# POV_2_0.net
KiCad netlist of a schematic drawn in EAGLE
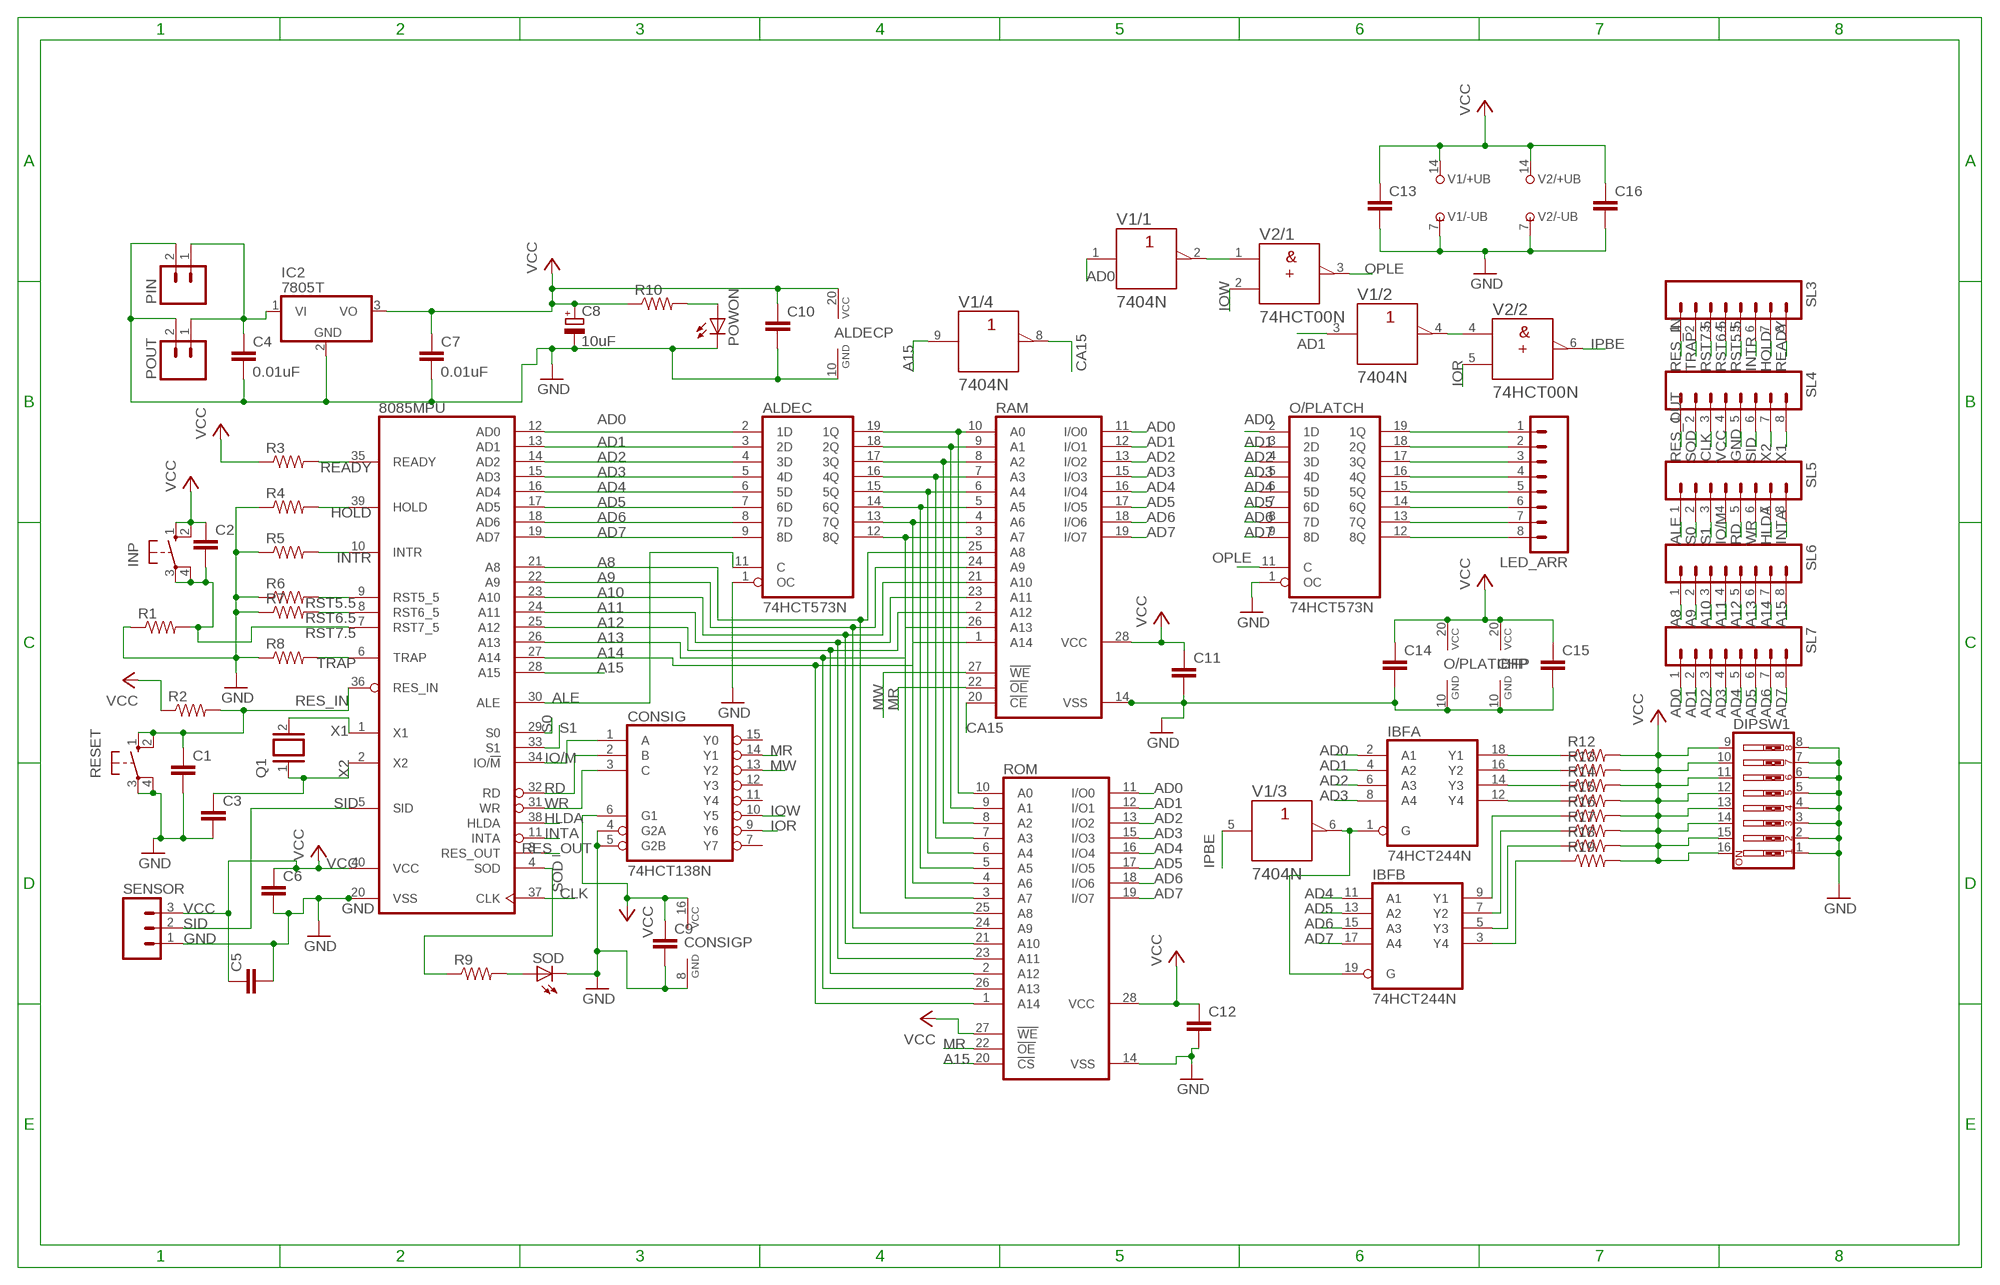
[diagram p0: schematic, sheet 1]

(export (version "E")
  (design (tool "Eeschema 10.0.6"))
  (components
    (comp (ref "8085MPU")
      (value "8085")
      (footprint "eagle-import:DIL40")
      (libsource (lib "eagle-import") (part "8085"))
    )
    (comp (ref "ALDEC")
      (value "74HCT573N")
      (footprint "eagle-import:DIL20")
      (libsource (lib "eagle-import") (part "74573NHCT"))
    )
    (comp (ref "C1")
      (value "C-EU025-024X044")
      (footprint "eagle-import:C025-024X044")
      (libsource (lib "eagle-import") (part "C-EU025-024X044"))
    )
    (comp (ref "C2")
      (value "C-EU025-024X044")
      (footprint "eagle-import:C025-024X044")
      (libsource (lib "eagle-import") (part "C-EU025-024X044"))
    )
    (comp (ref "C3")
      (value "C-EU025-024X044")
      (footprint "eagle-import:C025-024X044")
      (libsource (lib "eagle-import") (part "C-EU025-024X044"))
    )
    (comp (ref "C4")
      (value "0.01uF")
      (footprint "eagle-import:C025-024X044")
      (libsource (lib "eagle-import") (part "C-EU025-024X044"))
    )
    (comp (ref "C5")
      (value "C-EU025-024X044")
      (footprint "eagle-import:C025-024X044")
      (libsource (lib "eagle-import") (part "C-EU025-024X044"))
    )
    (comp (ref "C6")
      (value "C-EU025-024X044")
      (footprint "eagle-import:C025-024X044")
      (libsource (lib "eagle-import") (part "C-EU025-024X044"))
    )
    (comp (ref "C7")
      (value "0.01uF")
      (footprint "eagle-import:C025-024X044")
      (libsource (lib "eagle-import") (part "C-EU025-024X044"))
    )
    (comp (ref "C8")
      (value "10uF")
      (footprint "eagle-import:E2,5-6E")
      (libsource (lib "eagle-import") (part "CPOL-EUE2,5-6E"))
    )
    (comp (ref "C9")
      (value "C-EU025-024X044")
      (footprint "eagle-import:C025-024X044")
      (libsource (lib "eagle-import") (part "C-EU025-024X044"))
    )
    (comp (ref "C10")
      (value "C-EU025-024X044")
      (footprint "eagle-import:C025-024X044")
      (libsource (lib "eagle-import") (part "C-EU025-024X044"))
    )
    (comp (ref "C11")
      (value "C-EU025-024X044")
      (footprint "eagle-import:C025-024X044")
      (libsource (lib "eagle-import") (part "C-EU025-024X044"))
    )
    (comp (ref "C12")
      (value "C-EU025-024X044")
      (footprint "eagle-import:C025-024X044")
      (libsource (lib "eagle-import") (part "C-EU025-024X044"))
    )
    (comp (ref "C13")
      (value "C-EU025-024X044")
      (footprint "eagle-import:C025-024X044")
      (libsource (lib "eagle-import") (part "C-EU025-024X044"))
    )
    (comp (ref "C14")
      (value "C-EU025-024X044")
      (footprint "eagle-import:C025-024X044")
      (libsource (lib "eagle-import") (part "C-EU025-024X044"))
    )
    (comp (ref "C15")
      (value "C-EU025-024X044")
      (footprint "eagle-import:C025-024X044")
      (libsource (lib "eagle-import") (part "C-EU025-024X044"))
    )
    (comp (ref "C16")
      (value "C-EU025-024X044")
      (footprint "eagle-import:C025-024X044")
      (libsource (lib "eagle-import") (part "C-EU025-024X044"))
    )
    (comp (ref "CONSIG")
      (value "74HCT138N")
      (footprint "eagle-import:DIL16")
      (libsource (lib "eagle-import") (part "74138NHCT"))
    )
    (comp (ref "DIPSW1")
      (value "SW_DIP-8")
      (footprint "eagle-import:EDG-08")
      (libsource (lib "eagle-import") (part "SW_DIP-8"))
    )
    (comp (ref "IBF")
      (value "74HCT244N")
      (footprint "eagle-import:DIL20")
      (libsource (lib "eagle-import") (part "74244NHCT"))
    )
    (comp (ref "IC2")
      (value "7805T")
      (footprint "eagle-import:TO220H")
      (libsource (lib "eagle-import") (part "78T05"))
    )
    (comp (ref "INP")
      (value "10-XX")
      (footprint "eagle-import:B3F-10XX")
      (fields (field (name "MPN") "B3F-1000"))
      (libsource (lib "eagle-import") (part "10-XX"))
    )
    (comp (ref "LED_ARR")
      (value "M08")
      (footprint "eagle-import:08P")
      (libsource (lib "eagle-import") (part "M08"))
    )
    (comp (ref "O/PLATCH")
      (value "74HCT573N")
      (footprint "eagle-import:DIL20")
      (libsource (lib "eagle-import") (part "74573NHCT"))
    )
    (comp (ref "PIN")
      (value "M02")
      (footprint "eagle-import:02P")
      (libsource (lib "eagle-import") (part "M02"))
    )
    (comp (ref "POUT")
      (value "M02")
      (footprint "eagle-import:02P")
      (libsource (lib "eagle-import") (part "M02"))
    )
    (comp (ref "POWON")
      (value "LED5MM")
      (footprint "eagle-import:LED5MM")
      (libsource (lib "eagle-import") (part "LED5MM"))
    )
    (comp (ref "Q1")
      (value "XTAL/S")
      (footprint "eagle-import:QS")
      (libsource (lib "eagle-import") (part "XTAL/S"))
    )
    (comp (ref "R1")
      (value "R-US_0204/7")
      (footprint "eagle-import:0204_7")
      (libsource (lib "eagle-import") (part "R-US_0204/7"))
    )
    (comp (ref "R2")
      (value "R-US_0204/7")
      (footprint "eagle-import:0204_7")
      (libsource (lib "eagle-import") (part "R-US_0204/7"))
    )
    (comp (ref "R3")
      (value "R-US_0204/7")
      (footprint "eagle-import:0204_7")
      (libsource (lib "eagle-import") (part "R-US_0204/7"))
    )
    (comp (ref "R4")
      (value "R-US_0204/7")
      (footprint "eagle-import:0204_7")
      (libsource (lib "eagle-import") (part "R-US_0204/7"))
    )
    (comp (ref "R5")
      (value "R-US_0204/7")
      (footprint "eagle-import:0204_7")
      (libsource (lib "eagle-import") (part "R-US_0204/7"))
    )
    (comp (ref "R6")
      (value "R-US_0204/7")
      (footprint "eagle-import:0204_7")
      (libsource (lib "eagle-import") (part "R-US_0204/7"))
    )
    (comp (ref "R7")
      (value "R-US_0204/7")
      (footprint "eagle-import:0204_7")
      (libsource (lib "eagle-import") (part "R-US_0204/7"))
    )
    (comp (ref "R8")
      (value "R-US_0204/7")
      (footprint "eagle-import:0204_7")
      (libsource (lib "eagle-import") (part "R-US_0204/7"))
    )
    (comp (ref "R9")
      (value "R-US_0204/7")
      (footprint "eagle-import:0204_7")
      (libsource (lib "eagle-import") (part "R-US_0204/7"))
    )
    (comp (ref "R10")
      (value "R-US_0204/7")
      (footprint "eagle-import:0204_7")
      (libsource (lib "eagle-import") (part "R-US_0204/7"))
    )
    (comp (ref "R12")
      (value "R-US_0204/7")
      (footprint "eagle-import:0204_7")
      (libsource (lib "eagle-import") (part "R-US_0204/7"))
    )
    (comp (ref "R13")
      (value "R-US_0204/7")
      (footprint "eagle-import:0204_7")
      (libsource (lib "eagle-import") (part "R-US_0204/7"))
    )
    (comp (ref "R14")
      (value "R-US_0204/7")
      (footprint "eagle-import:0204_7")
      (libsource (lib "eagle-import") (part "R-US_0204/7"))
    )
    (comp (ref "R15")
      (value "R-US_0204/7")
      (footprint "eagle-import:0204_7")
      (libsource (lib "eagle-import") (part "R-US_0204/7"))
    )
    (comp (ref "R16")
      (value "R-US_0204/7")
      (footprint "eagle-import:0204_7")
      (libsource (lib "eagle-import") (part "R-US_0204/7"))
    )
    (comp (ref "R17")
      (value "R-US_0204/7")
      (footprint "eagle-import:0204_7")
      (libsource (lib "eagle-import") (part "R-US_0204/7"))
    )
    (comp (ref "R18")
      (value "R-US_0204/7")
      (footprint "eagle-import:0204_7")
      (libsource (lib "eagle-import") (part "R-US_0204/7"))
    )
    (comp (ref "R19")
      (value "R-US_0204/7")
      (footprint "eagle-import:0204_7")
      (libsource (lib "eagle-import") (part "R-US_0204/7"))
    )
    (comp (ref "RAM")
      (value "58C256P")
      (footprint "eagle-import:DIL28-6")
      (fields (field (name "MPN") "HN58C256AP85E"))
      (libsource (lib "eagle-import") (part "58C256P"))
    )
    (comp (ref "RESET")
      (value "10-XX")
      (footprint "eagle-import:B3F-10XX")
      (fields (field (name "MPN") "B3F-1000"))
      (libsource (lib "eagle-import") (part "10-XX"))
    )
    (comp (ref "ROM")
      (value "62256P")
      (footprint "eagle-import:DIL28-6")
      (libsource (lib "eagle-import") (part "62256P"))
    )
    (comp (ref "SENSOR")
      (value "M03")
      (footprint "eagle-import:03P")
      (libsource (lib "eagle-import") (part "M03"))
    )
    (comp (ref "SL3")
      (value "M08")
      (footprint "eagle-import:08P")
      (libsource (lib "eagle-import") (part "M08"))
    )
    (comp (ref "SL4")
      (value "M08")
      (footprint "eagle-import:08P")
      (libsource (lib "eagle-import") (part "M08"))
    )
    (comp (ref "SL5")
      (value "M08")
      (footprint "eagle-import:08P")
      (libsource (lib "eagle-import") (part "M08"))
    )
    (comp (ref "SL6")
      (value "M08")
      (footprint "eagle-import:08P")
      (libsource (lib "eagle-import") (part "M08"))
    )
    (comp (ref "SL7")
      (value "M08")
      (footprint "eagle-import:08P")
      (libsource (lib "eagle-import") (part "M08"))
    )
    (comp (ref "SOD")
      (value "LED5MM")
      (footprint "eagle-import:LED5MM")
      (libsource (lib "eagle-import") (part "LED5MM"))
    )
    (comp (ref "V1")
      (value "7404N")
      (footprint "eagle-import:DIL14")
      (libsource (lib "eagle-import") (part "7404N"))
    )
    (comp (ref "V2")
      (value "74HCT00N")
      (footprint "eagle-import:DIL14")
      (libsource (lib "eagle-import") (part "7400NHCT"))
    )
  )
  (nets
    (net (code "1") (name "/A8") (class "Default")
      (node (ref "8085MPU") (pin "21") (pinfunction "A8_21") (pintype "output"))
      (node (ref "RAM") (pin "25") (pinfunction "A8_25") (pintype "input"))
      (node (ref "ROM") (pin "25") (pinfunction "A8_25") (pintype "input"))
      (node (ref "SL6") (pin "1") (pinfunction "1_1") (pintype "passive"))
    )
    (net (code "2") (name "/A9") (class "Default")
      (node (ref "8085MPU") (pin "22") (pinfunction "A9_22") (pintype "output"))
      (node (ref "RAM") (pin "24") (pinfunction "A9_24") (pintype "input"))
      (node (ref "ROM") (pin "24") (pinfunction "A9_24") (pintype "input"))
      (node (ref "SL6") (pin "2") (pinfunction "2_2") (pintype "passive"))
    )
    (net (code "3") (name "/A10") (class "Default")
      (node (ref "8085MPU") (pin "23") (pinfunction "A10_23") (pintype "output"))
      (node (ref "RAM") (pin "21") (pinfunction "A10_21") (pintype "input"))
      (node (ref "ROM") (pin "21") (pinfunction "A10_21") (pintype "input"))
      (node (ref "SL6") (pin "3") (pinfunction "3_3") (pintype "passive"))
    )
    (net (code "4") (name "/A11") (class "Default")
      (node (ref "8085MPU") (pin "24") (pinfunction "A11_24") (pintype "output"))
      (node (ref "RAM") (pin "23") (pinfunction "A11_23") (pintype "input"))
      (node (ref "ROM") (pin "23") (pinfunction "A11_23") (pintype "input"))
      (node (ref "SL6") (pin "4") (pinfunction "4_4") (pintype "passive"))
    )
    (net (code "5") (name "/A12") (class "Default")
      (node (ref "8085MPU") (pin "25") (pinfunction "A12_25") (pintype "output"))
      (node (ref "RAM") (pin "2") (pinfunction "A12_2") (pintype "input"))
      (node (ref "ROM") (pin "2") (pinfunction "A12_2") (pintype "input"))
      (node (ref "SL6") (pin "5") (pinfunction "5_5") (pintype "passive"))
    )
    (net (code "6") (name "/A13") (class "Default")
      (node (ref "8085MPU") (pin "26") (pinfunction "A13_26") (pintype "output"))
      (node (ref "RAM") (pin "26") (pinfunction "A13_26") (pintype "input"))
      (node (ref "ROM") (pin "26") (pinfunction "A13_26") (pintype "input"))
      (node (ref "SL6") (pin "6") (pinfunction "6_6") (pintype "passive"))
    )
    (net (code "7") (name "/A14") (class "Default")
      (node (ref "8085MPU") (pin "27") (pinfunction "A14_27") (pintype "output"))
      (node (ref "RAM") (pin "1") (pinfunction "A14_1") (pintype "input"))
      (node (ref "ROM") (pin "1") (pinfunction "A14_1") (pintype "input"))
      (node (ref "SL6") (pin "7") (pinfunction "7_7") (pintype "passive"))
    )
    (net (code "8") (name "/A15") (class "Default")
      (node (ref "8085MPU") (pin "28") (pinfunction "A15_28") (pintype "output"))
      (node (ref "ROM") (pin "20") (pinfunction "~{CS}_20") (pintype "input"))
      (node (ref "SL6") (pin "8") (pinfunction "8_8") (pintype "passive"))
      (node (ref "V1") (pin "9") (pinfunction "A_9") (pintype "input"))
    )
    (net (code "9") (name "/AD0") (class "Default")
      (node (ref "8085MPU") (pin "12") (pinfunction "AD0_12") (pintype "bidirectional"))
      (node (ref "ALDEC") (pin "2") (pinfunction "1D_2") (pintype "input"))
      (node (ref "IBF") (pin "2") (pinfunction "A1_2") (pintype "input"))
      (node (ref "O/PLATCH") (pin "2") (pinfunction "1D_2") (pintype "input"))
      (node (ref "RAM") (pin "11") (pinfunction "I/O0_11") (pintype "tri_state"))
      (node (ref "ROM") (pin "11") (pinfunction "I/O0_11") (pintype "bidirectional"))
      (node (ref "SL7") (pin "1") (pinfunction "1_1") (pintype "passive"))
      (node (ref "V1") (pin "1") (pinfunction "A_1") (pintype "input"))
    )
    (net (code "10") (name "/AD1") (class "Default")
      (node (ref "8085MPU") (pin "13") (pinfunction "AD1_13") (pintype "bidirectional"))
      (node (ref "ALDEC") (pin "3") (pinfunction "2D_3") (pintype "input"))
      (node (ref "IBF") (pin "4") (pinfunction "A2_4") (pintype "input"))
      (node (ref "O/PLATCH") (pin "3") (pinfunction "2D_3") (pintype "input"))
      (node (ref "RAM") (pin "12") (pinfunction "I/O1_12") (pintype "tri_state"))
      (node (ref "ROM") (pin "12") (pinfunction "I/O1_12") (pintype "bidirectional"))
      (node (ref "SL7") (pin "2") (pinfunction "2_2") (pintype "passive"))
      (node (ref "V1") (pin "3") (pinfunction "A_3") (pintype "input"))
    )
    (net (code "11") (name "/AD2") (class "Default")
      (node (ref "8085MPU") (pin "14") (pinfunction "AD2_14") (pintype "bidirectional"))
      (node (ref "ALDEC") (pin "4") (pinfunction "3D_4") (pintype "input"))
      (node (ref "IBF") (pin "6") (pinfunction "A3_6") (pintype "input"))
      (node (ref "O/PLATCH") (pin "4") (pinfunction "3D_4") (pintype "input"))
      (node (ref "RAM") (pin "13") (pinfunction "I/O2_13") (pintype "tri_state"))
      (node (ref "ROM") (pin "13") (pinfunction "I/O2_13") (pintype "bidirectional"))
      (node (ref "SL7") (pin "3") (pinfunction "3_3") (pintype "passive"))
    )
    (net (code "12") (name "/AD3") (class "Default")
      (node (ref "8085MPU") (pin "15") (pinfunction "AD3_15") (pintype "bidirectional"))
      (node (ref "ALDEC") (pin "5") (pinfunction "4D_5") (pintype "input"))
      (node (ref "IBF") (pin "8") (pinfunction "A4_8") (pintype "input"))
      (node (ref "O/PLATCH") (pin "5") (pinfunction "4D_5") (pintype "input"))
      (node (ref "RAM") (pin "15") (pinfunction "I/O3_15") (pintype "tri_state"))
      (node (ref "ROM") (pin "15") (pinfunction "I/O3_15") (pintype "bidirectional"))
      (node (ref "SL7") (pin "4") (pinfunction "4_4") (pintype "passive"))
    )
    (net (code "13") (name "/AD4") (class "Default")
      (node (ref "8085MPU") (pin "16") (pinfunction "AD4_16") (pintype "bidirectional"))
      (node (ref "ALDEC") (pin "6") (pinfunction "5D_6") (pintype "input"))
      (node (ref "IBF") (pin "11") (pinfunction "A1_11") (pintype "input"))
      (node (ref "O/PLATCH") (pin "6") (pinfunction "5D_6") (pintype "input"))
      (node (ref "RAM") (pin "16") (pinfunction "I/O4_16") (pintype "tri_state"))
      (node (ref "ROM") (pin "16") (pinfunction "I/O4_16") (pintype "bidirectional"))
      (node (ref "SL7") (pin "5") (pinfunction "5_5") (pintype "passive"))
    )
    (net (code "14") (name "/AD5") (class "Default")
      (node (ref "8085MPU") (pin "17") (pinfunction "AD5_17") (pintype "bidirectional"))
      (node (ref "ALDEC") (pin "7") (pinfunction "6D_7") (pintype "input"))
      (node (ref "IBF") (pin "13") (pinfunction "A2_13") (pintype "input"))
      (node (ref "O/PLATCH") (pin "7") (pinfunction "6D_7") (pintype "input"))
      (node (ref "RAM") (pin "17") (pinfunction "I/O5_17") (pintype "tri_state"))
      (node (ref "ROM") (pin "17") (pinfunction "I/O5_17") (pintype "bidirectional"))
      (node (ref "SL7") (pin "6") (pinfunction "6_6") (pintype "passive"))
    )
    (net (code "15") (name "/AD6") (class "Default")
      (node (ref "8085MPU") (pin "18") (pinfunction "AD6_18") (pintype "bidirectional"))
      (node (ref "ALDEC") (pin "8") (pinfunction "7D_8") (pintype "input"))
      (node (ref "IBF") (pin "15") (pinfunction "A3_15") (pintype "input"))
      (node (ref "O/PLATCH") (pin "8") (pinfunction "7D_8") (pintype "input"))
      (node (ref "RAM") (pin "18") (pinfunction "I/O6_18") (pintype "tri_state"))
      (node (ref "ROM") (pin "18") (pinfunction "I/O6_18") (pintype "bidirectional"))
      (node (ref "SL7") (pin "7") (pinfunction "7_7") (pintype "passive"))
    )
    (net (code "16") (name "/AD7") (class "Default")
      (node (ref "8085MPU") (pin "19") (pinfunction "AD7_19") (pintype "bidirectional"))
      (node (ref "ALDEC") (pin "9") (pinfunction "8D_9") (pintype "input"))
      (node (ref "IBF") (pin "17") (pinfunction "A4_17") (pintype "input"))
      (node (ref "O/PLATCH") (pin "9") (pinfunction "8D_9") (pintype "input"))
      (node (ref "RAM") (pin "19") (pinfunction "I/O7_19") (pintype "tri_state"))
      (node (ref "ROM") (pin "19") (pinfunction "I/O7_19") (pintype "bidirectional"))
      (node (ref "SL7") (pin "8") (pinfunction "8_8") (pintype "passive"))
    )
    (net (code "17") (name "/ALE") (class "Default")
      (node (ref "8085MPU") (pin "30") (pinfunction "ALE_30") (pintype "output"))
      (node (ref "ALDEC") (pin "11") (pinfunction "C_11") (pintype "input"))
      (node (ref "SL5") (pin "1") (pinfunction "1_1") (pintype "passive"))
    )
    (net (code "18") (name "/CA15") (class "Default")
      (node (ref "RAM") (pin "20") (pinfunction "~{CE}_20") (pintype "input"))
      (node (ref "V1") (pin "8") (pinfunction "Y_8") (pintype "output"))
    )
    (net (code "19") (name "/CLK") (class "Default")
      (node (ref "8085MPU") (pin "37") (pinfunction "CLK_37") (pintype "output"))
      (node (ref "SL4") (pin "3") (pinfunction "3_3") (pintype "passive"))
    )
    (net (code "20") (name "/HLDA") (class "Default")
      (node (ref "8085MPU") (pin "38") (pinfunction "HLDA_38") (pintype "output"))
      (node (ref "SL5") (pin "7") (pinfunction "7_7") (pintype "passive"))
    )
    (net (code "21") (name "/HOLD") (class "Default")
      (node (ref "8085MPU") (pin "39") (pinfunction "HOLD_39") (pintype "input"))
      (node (ref "R4") (pin "2") (pinfunction "2_2") (pintype "passive"))
      (node (ref "SL3") (pin "7") (pinfunction "7_7") (pintype "passive"))
    )
    (net (code "22") (name "/INTA") (class "Default")
      (node (ref "8085MPU") (pin "11") (pinfunction "INTA_11") (pintype "output"))
      (node (ref "SL5") (pin "8") (pinfunction "8_8") (pintype "passive"))
    )
    (net (code "23") (name "/INTR") (class "Default")
      (node (ref "8085MPU") (pin "10") (pinfunction "INTR_10") (pintype "input"))
      (node (ref "R5") (pin "2") (pinfunction "2_2") (pintype "passive"))
      (node (ref "SL3") (pin "6") (pinfunction "6_6") (pintype "passive"))
    )
    (net (code "24") (name "/IOR") (class "Default")
      (node (ref "CONSIG") (pin "9") (pinfunction "Y6_9") (pintype "output"))
      (node (ref "V2") (pin "5") (pinfunction "B_5") (pintype "input"))
    )
    (net (code "25") (name "/IOW") (class "Default")
      (node (ref "CONSIG") (pin "10") (pinfunction "Y5_10") (pintype "output"))
      (node (ref "V2") (pin "2") (pinfunction "B_2") (pintype "input"))
    )
    (net (code "26") (name "/IO{slash}M") (class "Default")
      (node (ref "8085MPU") (pin "34") (pinfunction "IO/~{M}_34") (pintype "output"))
      (node (ref "CONSIG") (pin "1") (pinfunction "A_1") (pintype "input"))
      (node (ref "SL5") (pin "4") (pinfunction "4_4") (pintype "passive"))
    )
    (net (code "27") (name "/IPBE") (class "Default")
      (node (ref "V1") (pin "5") (pinfunction "A_5") (pintype "input"))
      (node (ref "V2") (pin "6") (pinfunction "Y_6") (pintype "output"))
    )
    (net (code "28") (name "/MR") (class "Default")
      (node (ref "CONSIG") (pin "14") (pinfunction "Y1_14") (pintype "output"))
      (node (ref "RAM") (pin "22") (pinfunction "~{OE}_22") (pintype "input"))
      (node (ref "ROM") (pin "22") (pinfunction "~{OE}_22") (pintype "input"))
    )
    (net (code "29") (name "/MW") (class "Default")
      (node (ref "CONSIG") (pin "13") (pinfunction "Y2_13") (pintype "output"))
      (node (ref "RAM") (pin "27") (pinfunction "~{WE}_27") (pintype "input"))
    )
    (net (code "30") (name "/OPLE") (class "Default")
      (node (ref "O/PLATCH") (pin "11") (pinfunction "C_11") (pintype "input"))
      (node (ref "V2") (pin "3") (pinfunction "Y_3") (pintype "output"))
    )
    (net (code "31") (name "/RD") (class "Default")
      (node (ref "8085MPU") (pin "32") (pinfunction "RD_32") (pintype "output"))
      (node (ref "CONSIG") (pin "2") (pinfunction "B_2") (pintype "input"))
      (node (ref "SL5") (pin "5") (pinfunction "5_5") (pintype "passive"))
    )
    (net (code "32") (name "/READY") (class "Default")
      (node (ref "8085MPU") (pin "35") (pinfunction "READY_35") (pintype "input"))
      (node (ref "R3") (pin "2") (pinfunction "2_2") (pintype "passive"))
      (node (ref "SL3") (pin "8") (pinfunction "8_8") (pintype "passive"))
    )
    (net (code "33") (name "/RES_IN") (class "Default")
      (node (ref "8085MPU") (pin "36") (pinfunction "RES_IN_36") (pintype "input"))
      (node (ref "C1") (pin "1") (pinfunction "1_1") (pintype "passive"))
      (node (ref "R2") (pin "2") (pinfunction "2_2") (pintype "passive"))
      (node (ref "RESET") (pin "1") (pinfunction "S_1") (pintype "passive"))
      (node (ref "RESET") (pin "2") (pinfunction "S1_2") (pintype "passive"))
      (node (ref "SL3") (pin "1") (pinfunction "1_1") (pintype "passive"))
    )
    (net (code "34") (name "/RES_OUT") (class "Default")
      (node (ref "8085MPU") (pin "3") (pinfunction "RES_OUT_3") (pintype "output"))
      (node (ref "SL4") (pin "1") (pinfunction "1_1") (pintype "passive"))
    )
    (net (code "35") (name "/RST5.5") (class "Default")
      (node (ref "8085MPU") (pin "9") (pinfunction "RST5_5_9") (pintype "input"))
      (node (ref "R6") (pin "2") (pinfunction "2_2") (pintype "passive"))
      (node (ref "SL3") (pin "5") (pinfunction "5_5") (pintype "passive"))
    )
    (net (code "36") (name "/RST6.5") (class "Default")
      (node (ref "8085MPU") (pin "8") (pinfunction "RST6_5_8") (pintype "input"))
      (node (ref "R7") (pin "2") (pinfunction "2_2") (pintype "passive"))
      (node (ref "SL3") (pin "4") (pinfunction "4_4") (pintype "passive"))
    )
    (net (code "37") (name "/RST7.5") (class "Default")
      (node (ref "8085MPU") (pin "7") (pinfunction "RST7_5_7") (pintype "input"))
      (node (ref "C2") (pin "2") (pinfunction "2_2") (pintype "passive"))
      (node (ref "INP") (pin "3") (pinfunction "P_3") (pintype "passive"))
      (node (ref "INP") (pin "4") (pinfunction "P1_4") (pintype "passive"))
      (node (ref "R1") (pin "2") (pinfunction "2_2") (pintype "passive"))
      (node (ref "SL3") (pin "3") (pinfunction "3_3") (pintype "passive"))
    )
    (net (code "38") (name "/S0") (class "Default")
      (node (ref "8085MPU") (pin "29") (pinfunction "S0_29") (pintype "output"))
      (node (ref "SL5") (pin "2") (pinfunction "2_2") (pintype "passive"))
    )
    (net (code "39") (name "/S1") (class "Default")
      (node (ref "8085MPU") (pin "33") (pinfunction "S1_33") (pintype "output"))
      (node (ref "SL5") (pin "3") (pinfunction "3_3") (pintype "passive"))
    )
    (net (code "40") (name "/SID") (class "Default")
      (node (ref "8085MPU") (pin "5") (pinfunction "SID_5") (pintype "input"))
      (node (ref "SENSOR") (pin "2") (pinfunction "2_2") (pintype "passive"))
      (node (ref "SL4") (pin "6") (pinfunction "6_6") (pintype "passive"))
    )
    (net (code "41") (name "/SOD") (class "Default")
      (node (ref "8085MPU") (pin "4") (pinfunction "SOD_4") (pintype "output"))
      (node (ref "R9") (pin "1") (pinfunction "1_1") (pintype "passive"))
      (node (ref "SL4") (pin "2") (pinfunction "2_2") (pintype "passive"))
    )
    (net (code "42") (name "/TRAP") (class "Default")
      (node (ref "8085MPU") (pin "6") (pinfunction "TRAP_6") (pintype "input"))
      (node (ref "R8") (pin "2") (pinfunction "2_2") (pintype "passive"))
      (node (ref "SL3") (pin "2") (pinfunction "2_2") (pintype "passive"))
    )
    (net (code "43") (name "/WR") (class "Default")
      (node (ref "8085MPU") (pin "31") (pinfunction "WR_31") (pintype "output"))
      (node (ref "CONSIG") (pin "3") (pinfunction "C_3") (pintype "input"))
      (node (ref "SL5") (pin "6") (pinfunction "6_6") (pintype "passive"))
    )
    (net (code "44") (name "/X1") (class "Default")
      (node (ref "8085MPU") (pin "1") (pinfunction "X1_1") (pintype "input"))
      (node (ref "Q1") (pin "2") (pinfunction "2_2") (pintype "passive"))
      (node (ref "SL4") (pin "8") (pinfunction "8_8") (pintype "passive"))
    )
    (net (code "45") (name "/X2") (class "Default")
      (node (ref "8085MPU") (pin "2") (pinfunction "X2_2") (pintype "input"))
      (node (ref "C3") (pin "1") (pinfunction "1_1") (pintype "passive"))
      (node (ref "Q1") (pin "1") (pinfunction "1_1") (pintype "passive"))
      (node (ref "SL4") (pin "7") (pinfunction "7_7") (pintype "passive"))
    )
    (net (code "46") (name "GND") (class "Default")
      (node (ref "8085MPU") (pin "20") (pinfunction "VSS_20") (pintype "power_in"))
      (node (ref "ALDEC") (pin "1") (pinfunction "OC_1") (pintype "input"))
      (node (ref "ALDEC") (pin "10") (pinfunction "GND_10") (pintype "power_in"))
      (node (ref "C1") (pin "2") (pinfunction "2_2") (pintype "passive"))
      (node (ref "C10") (pin "2") (pinfunction "2_2") (pintype "passive"))
      (node (ref "C11") (pin "2") (pinfunction "2_2") (pintype "passive"))
      (node (ref "C12") (pin "2") (pinfunction "2_2") (pintype "passive"))
      (node (ref "C13") (pin "2") (pinfunction "2_2") (pintype "passive"))
      (node (ref "C14") (pin "2") (pinfunction "2_2") (pintype "passive"))
      (node (ref "C15") (pin "2") (pinfunction "2_2") (pintype "passive"))
      (node (ref "C16") (pin "2") (pinfunction "2_2") (pintype "passive"))
      (node (ref "C3") (pin "2") (pinfunction "2_2") (pintype "passive"))
      (node (ref "C4") (pin "2") (pinfunction "2_2") (pintype "passive"))
      (node (ref "C5") (pin "2") (pinfunction "2_2") (pintype "passive"))
      (node (ref "C6") (pin "2") (pinfunction "2_2") (pintype "passive"))
      (node (ref "C7") (pin "2") (pinfunction "2_2") (pintype "passive"))
      (node (ref "C8") (pin "-") (pinfunction "-_-") (pintype "passive"))
      (node (ref "C9") (pin "2") (pinfunction "2_2") (pintype "passive"))
      (node (ref "CONSIG") (pin "4") (pinfunction "G2A_4") (pintype "input"))
      (node (ref "CONSIG") (pin "5") (pinfunction "G2B_5") (pintype "input"))
      (node (ref "CONSIG") (pin "8") (pinfunction "GND_8") (pintype "power_in"))
      (node (ref "DIPSW1") (pin "1") (pinfunction "1_1") (pintype "passive"))
      (node (ref "DIPSW1") (pin "2") (pinfunction "2_2") (pintype "passive"))
      (node (ref "DIPSW1") (pin "3") (pinfunction "3_3") (pintype "passive"))
      (node (ref "DIPSW1") (pin "4") (pinfunction "4_4") (pintype "passive"))
      (node (ref "DIPSW1") (pin "5") (pinfunction "5_5") (pintype "passive"))
      (node (ref "DIPSW1") (pin "6") (pinfunction "6_6") (pintype "passive"))
      (node (ref "DIPSW1") (pin "7") (pinfunction "7_7") (pintype "passive"))
      (node (ref "DIPSW1") (pin "8") (pinfunction "8_8") (pintype "passive"))
      (node (ref "IBF") (pin "10") (pinfunction "GND_10") (pintype "power_in"))
      (node (ref "IC2") (pin "2") (pinfunction "GND_2") (pintype "passive"))
      (node (ref "O/PLATCH") (pin "1") (pinfunction "OC_1") (pintype "input"))
      (node (ref "O/PLATCH") (pin "10") (pinfunction "GND_10") (pintype "power_in"))
      (node (ref "PIN") (pin "2") (pinfunction "2_2") (pintype "passive"))
      (node (ref "POUT") (pin "2") (pinfunction "2_2") (pintype "passive"))
      (node (ref "POWON") (pin "K") (pinfunction "C_K") (pintype "passive"))
      (node (ref "R1") (pin "1") (pinfunction "1_1") (pintype "passive"))
      (node (ref "R4") (pin "1") (pinfunction "1_1") (pintype "passive"))
      (node (ref "R5") (pin "1") (pinfunction "1_1") (pintype "passive"))
      (node (ref "R6") (pin "1") (pinfunction "1_1") (pintype "passive"))
      (node (ref "R7") (pin "1") (pinfunction "1_1") (pintype "passive"))
      (node (ref "R8") (pin "1") (pinfunction "1_1") (pintype "passive"))
      (node (ref "RAM") (pin "14") (pinfunction "VSS_14") (pintype "power_in"))
      (node (ref "RESET") (pin "3") (pinfunction "P_3") (pintype "passive"))
      (node (ref "RESET") (pin "4") (pinfunction "P1_4") (pintype "passive"))
      (node (ref "ROM") (pin "14") (pinfunction "VSS_14") (pintype "power_in"))
      (node (ref "SENSOR") (pin "1") (pinfunction "1_1") (pintype "passive"))
      (node (ref "SL4") (pin "5") (pinfunction "5_5") (pintype "passive"))
      (node (ref "SOD") (pin "K") (pinfunction "C_K") (pintype "passive"))
      (node (ref "V1") (pin "7") (pinfunction "-UB_7") (pintype "power_in"))
      (node (ref "V2") (pin "7") (pinfunction "-UB_7") (pintype "power_in"))
    )
    (net (code "47") (name "Net-(ALDECA-1Q)") (class "Default")
      (node (ref "ALDEC") (pin "19") (pinfunction "1Q_19") (pintype "tri_state"))
      (node (ref "RAM") (pin "10") (pinfunction "A0_10") (pintype "input"))
      (node (ref "ROM") (pin "10") (pinfunction "A0_10") (pintype "input"))
    )
    (net (code "48") (name "Net-(ALDECA-2Q)") (class "Default")
      (node (ref "ALDEC") (pin "18") (pinfunction "2Q_18") (pintype "tri_state"))
      (node (ref "RAM") (pin "9") (pinfunction "A1_9") (pintype "input"))
      (node (ref "ROM") (pin "9") (pinfunction "A1_9") (pintype "input"))
    )
    (net (code "49") (name "Net-(ALDECA-3Q)") (class "Default")
      (node (ref "ALDEC") (pin "17") (pinfunction "3Q_17") (pintype "tri_state"))
      (node (ref "RAM") (pin "8") (pinfunction "A2_8") (pintype "input"))
      (node (ref "ROM") (pin "8") (pinfunction "A2_8") (pintype "input"))
    )
    (net (code "50") (name "Net-(ALDECA-4Q)") (class "Default")
      (node (ref "ALDEC") (pin "16") (pinfunction "4Q_16") (pintype "tri_state"))
      (node (ref "RAM") (pin "7") (pinfunction "A3_7") (pintype "input"))
      (node (ref "ROM") (pin "7") (pinfunction "A3_7") (pintype "input"))
    )
    (net (code "51") (name "Net-(ALDECA-5Q)") (class "Default")
      (node (ref "ALDEC") (pin "15") (pinfunction "5Q_15") (pintype "tri_state"))
      (node (ref "RAM") (pin "6") (pinfunction "A4_6") (pintype "input"))
      (node (ref "ROM") (pin "6") (pinfunction "A4_6") (pintype "input"))
    )
    (net (code "52") (name "Net-(ALDECA-6Q)") (class "Default")
      (node (ref "ALDEC") (pin "14") (pinfunction "6Q_14") (pintype "tri_state"))
      (node (ref "RAM") (pin "5") (pinfunction "A5_5") (pintype "input"))
      (node (ref "ROM") (pin "5") (pinfunction "A5_5") (pintype "input"))
    )
    (net (code "53") (name "Net-(ALDECA-7Q)") (class "Default")
      (node (ref "ALDEC") (pin "13") (pinfunction "7Q_13") (pintype "tri_state"))
      (node (ref "RAM") (pin "4") (pinfunction "A6_4") (pintype "input"))
      (node (ref "ROM") (pin "4") (pinfunction "A6_4") (pintype "input"))
    )
    (net (code "54") (name "Net-(ALDECA-8Q)") (class "Default")
      (node (ref "ALDEC") (pin "12") (pinfunction "8Q_12") (pintype "tri_state"))
      (node (ref "RAM") (pin "3") (pinfunction "A7_3") (pintype "input"))
      (node (ref "ROM") (pin "3") (pinfunction "A7_3") (pintype "input"))
    )
    (net (code "55") (name "Net-(IBFA-G)") (class "Default")
      (node (ref "IBF") (pin "1") (pinfunction "G_1") (pintype "input"))
      (node (ref "IBF") (pin "19") (pinfunction "G_19") (pintype "input"))
      (node (ref "V1") (pin "6") (pinfunction "Y_6") (pintype "output"))
    )
    (net (code "56") (name "Net-(IBFA-Y1)") (class "Default")
      (node (ref "IBF") (pin "18") (pinfunction "Y1_18") (pintype "tri_state"))
      (node (ref "R12") (pin "1") (pinfunction "1_1") (pintype "passive"))
    )
    (net (code "57") (name "Net-(IBFA-Y2)") (class "Default")
      (node (ref "IBF") (pin "16") (pinfunction "Y2_16") (pintype "tri_state"))
      (node (ref "R13") (pin "1") (pinfunction "1_1") (pintype "passive"))
    )
    (net (code "58") (name "Net-(IBFA-Y3)") (class "Default")
      (node (ref "IBF") (pin "14") (pinfunction "Y3_14") (pintype "tri_state"))
      (node (ref "R14") (pin "1") (pinfunction "1_1") (pintype "passive"))
    )
    (net (code "59") (name "Net-(IBFA-Y4)") (class "Default")
      (node (ref "IBF") (pin "12") (pinfunction "Y4_12") (pintype "tri_state"))
      (node (ref "R15") (pin "1") (pinfunction "1_1") (pintype "passive"))
    )
    (net (code "60") (name "Net-(IBFB-Y1)") (class "Default")
      (node (ref "IBF") (pin "9") (pinfunction "Y1_9") (pintype "tri_state"))
      (node (ref "R16") (pin "1") (pinfunction "1_1") (pintype "passive"))
    )
    (net (code "61") (name "Net-(IBFB-Y2)") (class "Default")
      (node (ref "IBF") (pin "7") (pinfunction "Y2_7") (pintype "tri_state"))
      (node (ref "R17") (pin "1") (pinfunction "1_1") (pintype "passive"))
    )
    (net (code "62") (name "Net-(IBFB-Y3)") (class "Default")
      (node (ref "IBF") (pin "5") (pinfunction "Y3_5") (pintype "tri_state"))
      (node (ref "R18") (pin "1") (pinfunction "1_1") (pintype "passive"))
    )
    (net (code "63") (name "Net-(IBFB-Y4)") (class "Default")
      (node (ref "IBF") (pin "3") (pinfunction "Y4_3") (pintype "tri_state"))
      (node (ref "R19") (pin "1") (pinfunction "1_1") (pintype "passive"))
    )
    (net (code "64") (name "Net-(IC2-VI)") (class "Default")
      (node (ref "C4") (pin "1") (pinfunction "1_1") (pintype "passive"))
      (node (ref "IC2") (pin "1") (pinfunction "VI_1") (pintype "input"))
      (node (ref "PIN") (pin "1") (pinfunction "1_1") (pintype "passive"))
      (node (ref "POUT") (pin "1") (pinfunction "1_1") (pintype "passive"))
    )
    (net (code "65") (name "Net-(O/PLATCHA-1Q)") (class "Default")
      (node (ref "LED_ARR") (pin "1") (pinfunction "1_1") (pintype "passive"))
      (node (ref "O/PLATCH") (pin "19") (pinfunction "1Q_19") (pintype "tri_state"))
    )
    (net (code "66") (name "Net-(O/PLATCHA-2Q)") (class "Default")
      (node (ref "LED_ARR") (pin "2") (pinfunction "2_2") (pintype "passive"))
      (node (ref "O/PLATCH") (pin "18") (pinfunction "2Q_18") (pintype "tri_state"))
    )
    (net (code "67") (name "Net-(O/PLATCHA-3Q)") (class "Default")
      (node (ref "LED_ARR") (pin "3") (pinfunction "3_3") (pintype "passive"))
      (node (ref "O/PLATCH") (pin "17") (pinfunction "3Q_17") (pintype "tri_state"))
    )
    (net (code "68") (name "Net-(O/PLATCHA-4Q)") (class "Default")
      (node (ref "LED_ARR") (pin "4") (pinfunction "4_4") (pintype "passive"))
      (node (ref "O/PLATCH") (pin "16") (pinfunction "4Q_16") (pintype "tri_state"))
    )
    (net (code "69") (name "Net-(O/PLATCHA-5Q)") (class "Default")
      (node (ref "LED_ARR") (pin "5") (pinfunction "5_5") (pintype "passive"))
      (node (ref "O/PLATCH") (pin "15") (pinfunction "5Q_15") (pintype "tri_state"))
    )
    (net (code "70") (name "Net-(O/PLATCHA-6Q)") (class "Default")
      (node (ref "LED_ARR") (pin "6") (pinfunction "6_6") (pintype "passive"))
      (node (ref "O/PLATCH") (pin "14") (pinfunction "6Q_14") (pintype "tri_state"))
    )
    (net (code "71") (name "Net-(O/PLATCHA-7Q)") (class "Default")
      (node (ref "LED_ARR") (pin "7") (pinfunction "7_7") (pintype "passive"))
      (node (ref "O/PLATCH") (pin "13") (pinfunction "7Q_13") (pintype "tri_state"))
    )
    (net (code "72") (name "Net-(O/PLATCHA-8Q)") (class "Default")
      (node (ref "LED_ARR") (pin "8") (pinfunction "8_8") (pintype "passive"))
      (node (ref "O/PLATCH") (pin "12") (pinfunction "8Q_12") (pintype "tri_state"))
    )
    (net (code "73") (name "Net-(POWON-PadA)") (class "Default")
      (node (ref "POWON") (pin "A") (pinfunction "A_A") (pintype "passive"))
      (node (ref "R10") (pin "2") (pinfunction "2_2") (pintype "passive"))
    )
    (net (code "74") (name "Net-(R9-Pad2)") (class "Default")
      (node (ref "R9") (pin "2") (pinfunction "2_2") (pintype "passive"))
      (node (ref "SOD") (pin "A") (pinfunction "A_A") (pintype "passive"))
    )
    (net (code "75") (name "Net-(V1C-Y)") (class "Default")
      (node (ref "V1") (pin "2") (pinfunction "Y_2") (pintype "output"))
      (node (ref "V2") (pin "1") (pinfunction "A_1") (pintype "input"))
    )
    (net (code "76") (name "Net-(V1D-Y)") (class "Default")
      (node (ref "V1") (pin "4") (pinfunction "Y_4") (pintype "output"))
      (node (ref "V2") (pin "4") (pinfunction "A_4") (pintype "input"))
    )
    (net (code "77") (name "VCC") (class "Default")
      (node (ref "8085MPU") (pin "40") (pinfunction "VCC_40") (pintype "power_in"))
      (node (ref "ALDEC") (pin "20") (pinfunction "VCC_20") (pintype "power_in"))
      (node (ref "C10") (pin "1") (pinfunction "1_1") (pintype "passive"))
      (node (ref "C11") (pin "1") (pinfunction "1_1") (pintype "passive"))
      (node (ref "C12") (pin "1") (pinfunction "1_1") (pintype "passive"))
      (node (ref "C13") (pin "1") (pinfunction "1_1") (pintype "passive"))
      (node (ref "C14") (pin "1") (pinfunction "1_1") (pintype "passive"))
      (node (ref "C15") (pin "1") (pinfunction "1_1") (pintype "passive"))
      (node (ref "C16") (pin "1") (pinfunction "1_1") (pintype "passive"))
      (node (ref "C2") (pin "1") (pinfunction "1_1") (pintype "passive"))
      (node (ref "C5") (pin "1") (pinfunction "1_1") (pintype "passive"))
      (node (ref "C6") (pin "1") (pinfunction "1_1") (pintype "passive"))
      (node (ref "C7") (pin "1") (pinfunction "1_1") (pintype "passive"))
      (node (ref "C8") (pin "+") (pinfunction "+_+") (pintype "passive"))
      (node (ref "C9") (pin "1") (pinfunction "1_1") (pintype "passive"))
      (node (ref "CONSIG") (pin "16") (pinfunction "VCC_16") (pintype "power_in"))
      (node (ref "CONSIG") (pin "6") (pinfunction "G1_6") (pintype "input"))
      (node (ref "DIPSW1") (pin "10") (pinfunction "10_10") (pintype "passive"))
      (node (ref "DIPSW1") (pin "11") (pinfunction "11_11") (pintype "passive"))
      (node (ref "DIPSW1") (pin "12") (pinfunction "12_12") (pintype "passive"))
      (node (ref "DIPSW1") (pin "13") (pinfunction "13_13") (pintype "passive"))
      (node (ref "DIPSW1") (pin "14") (pinfunction "14_14") (pintype "passive"))
      (node (ref "DIPSW1") (pin "15") (pinfunction "15_15") (pintype "passive"))
      (node (ref "DIPSW1") (pin "16") (pinfunction "16_16") (pintype "passive"))
      (node (ref "DIPSW1") (pin "9") (pinfunction "9_9") (pintype "passive"))
      (node (ref "IBF") (pin "20") (pinfunction "VCC_20") (pintype "power_in"))
      (node (ref "IC2") (pin "3") (pinfunction "VO_3") (pintype "passive"))
      (node (ref "INP") (pin "1") (pinfunction "S_1") (pintype "passive"))
      (node (ref "INP") (pin "2") (pinfunction "S1_2") (pintype "passive"))
      (node (ref "O/PLATCH") (pin "20") (pinfunction "VCC_20") (pintype "power_in"))
      (node (ref "R10") (pin "1") (pinfunction "1_1") (pintype "passive"))
      (node (ref "R12") (pin "2") (pinfunction "2_2") (pintype "passive"))
      (node (ref "R13") (pin "2") (pinfunction "2_2") (pintype "passive"))
      (node (ref "R14") (pin "2") (pinfunction "2_2") (pintype "passive"))
      (node (ref "R15") (pin "2") (pinfunction "2_2") (pintype "passive"))
      (node (ref "R16") (pin "2") (pinfunction "2_2") (pintype "passive"))
      (node (ref "R17") (pin "2") (pinfunction "2_2") (pintype "passive"))
      (node (ref "R18") (pin "2") (pinfunction "2_2") (pintype "passive"))
      (node (ref "R19") (pin "2") (pinfunction "2_2") (pintype "passive"))
      (node (ref "R2") (pin "1") (pinfunction "1_1") (pintype "passive"))
      (node (ref "R3") (pin "1") (pinfunction "1_1") (pintype "passive"))
      (node (ref "RAM") (pin "28") (pinfunction "VCC_28") (pintype "power_in"))
      (node (ref "ROM") (pin "27") (pinfunction "~{WE}_27") (pintype "input"))
      (node (ref "ROM") (pin "28") (pinfunction "VCC_28") (pintype "power_in"))
      (node (ref "SENSOR") (pin "3") (pinfunction "3_3") (pintype "passive"))
      (node (ref "SL4") (pin "4") (pinfunction "4_4") (pintype "passive"))
      (node (ref "V1") (pin "14") (pinfunction "+UB_14") (pintype "power_in"))
      (node (ref "V2") (pin "14") (pinfunction "+UB_14") (pintype "power_in"))
    )
    (net (code "78") (name "unconnected-(CONSIGA-Y0-Pad15)") (class "Default")
      (node (ref "CONSIG") (pin "15") (pinfunction "Y0_15") (pintype "output"))
    )
    (net (code "79") (name "unconnected-(CONSIGA-Y3-Pad12)") (class "Default")
      (node (ref "CONSIG") (pin "12") (pinfunction "Y3_12") (pintype "output"))
    )
    (net (code "80") (name "unconnected-(CONSIGA-Y4-Pad11)") (class "Default")
      (node (ref "CONSIG") (pin "11") (pinfunction "Y4_11") (pintype "output"))
    )
    (net (code "81") (name "unconnected-(CONSIGA-Y7-Pad7)") (class "Default")
      (node (ref "CONSIG") (pin "7") (pinfunction "Y7_7") (pintype "output"))
    )
  )
)
